# GSP.net
KiCad netlist of a schematic drawn in EAGLE
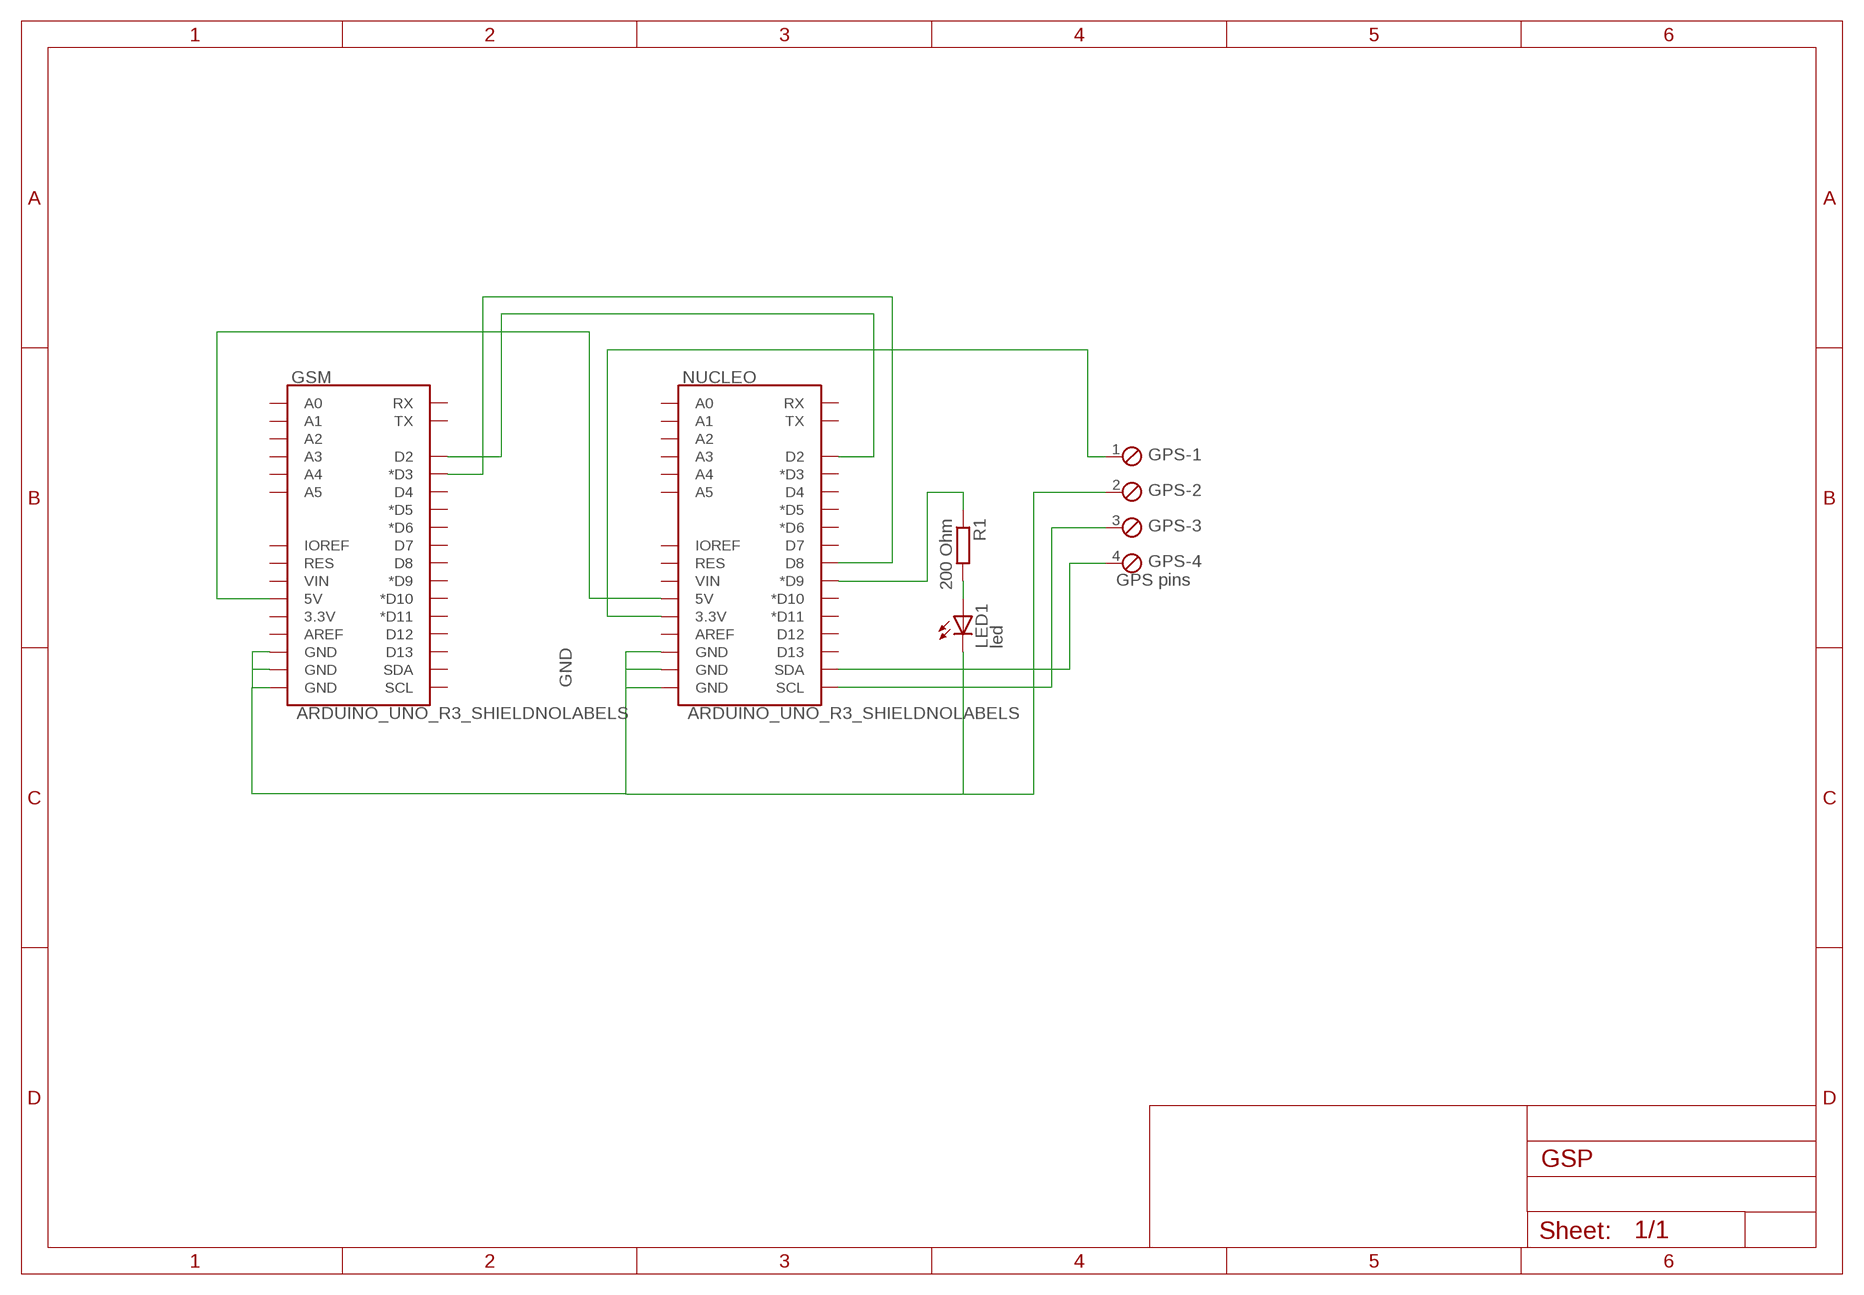
[diagram p0: schematic, sheet 1]

(export (version "E")
  (design (tool "Eeschema 10.0.6"))
  (components
    (comp (ref "GPS")
      (value "GPS pins")
      (footprint "eagle-import:4POL254")
      (libsource (lib "eagle-import") (part "MPT4"))
    )
    (comp (ref "GSM")
      (value "ARDUINO_UNO_R3_SHIELDNOLABELS")
      (footprint "eagle-import:UNO_R3_SHIELD_NOLABELS")
      (libsource (lib "eagle-import") (part "ARDUINO_UNO_R3_SHIELDNOLABELS"))
    )
    (comp (ref "LED1")
      (value "led")
      (footprint "eagle-import:LED3MM")
      (libsource (lib "eagle-import") (part "LED3MM"))
    )
    (comp (ref "NUCLEO")
      (value "ARDUINO_UNO_R3_SHIELDNOLABELS")
      (footprint "eagle-import:UNO_R3_SHIELD_NOLABELS")
      (libsource (lib "eagle-import") (part "ARDUINO_UNO_R3_SHIELDNOLABELS"))
    )
    (comp (ref "R1")
      (value "200 Ohm")
      (footprint "eagle-import:0204_5")
      (libsource (lib "eagle-import") (part "R-EU_0204/5"))
    )
  )
  (nets
    (net (code "1") (name "/GND") (class "Default")
      (node (ref "GPS") (pin "2") (pinfunction "1_2") (pintype "passive"))
      (node (ref "GSM") (pin "GND@0") (pinfunction "GND_GND@0") (pintype "bidirectional"))
      (node (ref "GSM") (pin "GND@1") (pinfunction "GND_GND@1") (pintype "bidirectional"))
      (node (ref "GSM") (pin "GND@2") (pinfunction "GND_GND@2") (pintype "bidirectional"))
      (node (ref "LED1") (pin "K") (pinfunction "C_K") (pintype "passive"))
      (node (ref "NUCLEO") (pin "GND@0") (pinfunction "GND_GND@0") (pintype "bidirectional"))
      (node (ref "NUCLEO") (pin "GND@1") (pinfunction "GND_GND@1") (pintype "bidirectional"))
      (node (ref "NUCLEO") (pin "GND@2") (pinfunction "GND_GND@2") (pintype "bidirectional"))
    )
    (net (code "2") (name "Net-(GPS-Pad1)") (class "Default")
      (node (ref "GPS") (pin "1") (pinfunction "1_1") (pintype "passive"))
      (node (ref "NUCLEO") (pin "3.3V") (pinfunction "3.3V_3.3V") (pintype "bidirectional"))
    )
    (net (code "3") (name "Net-(GPSC-1)") (class "Default")
      (node (ref "GPS") (pin "3") (pinfunction "1_3") (pintype "passive"))
      (node (ref "NUCLEO") (pin "SCL") (pinfunction "SCL_SCL") (pintype "bidirectional"))
    )
    (net (code "4") (name "Net-(GPSD-1)") (class "Default")
      (node (ref "GPS") (pin "4") (pinfunction "1_4") (pintype "passive"))
      (node (ref "NUCLEO") (pin "SDA") (pinfunction "SDA_SDA") (pintype "bidirectional"))
    )
    (net (code "5") (name "Net-(GSM-*D3)") (class "Default")
      (node (ref "GSM") (pin "D3") (pinfunction "*D3_D3") (pintype "bidirectional"))
      (node (ref "NUCLEO") (pin "D8") (pinfunction "D8_D8") (pintype "bidirectional"))
    )
    (net (code "6") (name "Net-(GSM-Pad5V)") (class "Default")
      (node (ref "GSM") (pin "5V") (pinfunction "5V_5V") (pintype "bidirectional"))
      (node (ref "NUCLEO") (pin "5V") (pinfunction "5V_5V") (pintype "bidirectional"))
    )
    (net (code "7") (name "Net-(GSM-PadD2)") (class "Default")
      (node (ref "GSM") (pin "D2") (pinfunction "D2_D2") (pintype "bidirectional"))
      (node (ref "NUCLEO") (pin "D2") (pinfunction "D2_D2") (pintype "bidirectional"))
    )
    (net (code "8") (name "Net-(LED1-PadA)") (class "Default")
      (node (ref "LED1") (pin "A") (pinfunction "A_A") (pintype "passive"))
      (node (ref "R1") (pin "2") (pinfunction "2_2") (pintype "passive"))
    )
    (net (code "9") (name "Net-(NUCLEO-*D9)") (class "Default")
      (node (ref "NUCLEO") (pin "D9") (pinfunction "*D9_D9") (pintype "bidirectional"))
      (node (ref "R1") (pin "1") (pinfunction "1_1") (pintype "passive"))
    )
    (net (code "10") (name "unconnected-(GSM-*D5-PadD5)") (class "Default")
      (node (ref "GSM") (pin "D5") (pinfunction "*D5_D5") (pintype "bidirectional"))
    )
    (net (code "11") (name "unconnected-(GSM-*D6-PadD6)") (class "Default")
      (node (ref "GSM") (pin "D6") (pinfunction "*D6_D6") (pintype "bidirectional"))
    )
    (net (code "12") (name "unconnected-(GSM-*D9-PadD9)") (class "Default")
      (node (ref "GSM") (pin "D9") (pinfunction "*D9_D9") (pintype "bidirectional"))
    )
    (net (code "13") (name "unconnected-(GSM-*D10-PadD10)") (class "Default")
      (node (ref "GSM") (pin "D10") (pinfunction "*D10_D10") (pintype "bidirectional"))
    )
    (net (code "14") (name "unconnected-(GSM-*D11-PadD11)") (class "Default")
      (node (ref "GSM") (pin "D11") (pinfunction "*D11_D11") (pintype "bidirectional"))
    )
    (net (code "15") (name "unconnected-(GSM-Pad3.3V)") (class "Default")
      (node (ref "GSM") (pin "3.3V") (pinfunction "3.3V_3.3V") (pintype "bidirectional"))
    )
    (net (code "16") (name "unconnected-(GSM-PadA0)") (class "Default")
      (node (ref "GSM") (pin "A0") (pinfunction "A0_A0") (pintype "bidirectional"))
    )
    (net (code "17") (name "unconnected-(GSM-PadA1)") (class "Default")
      (node (ref "GSM") (pin "A1") (pinfunction "A1_A1") (pintype "bidirectional"))
    )
    (net (code "18") (name "unconnected-(GSM-PadA2)") (class "Default")
      (node (ref "GSM") (pin "A2") (pinfunction "A2_A2") (pintype "bidirectional"))
    )
    (net (code "19") (name "unconnected-(GSM-PadA3)") (class "Default")
      (node (ref "GSM") (pin "A3") (pinfunction "A3_A3") (pintype "bidirectional"))
    )
    (net (code "20") (name "unconnected-(GSM-PadA4)") (class "Default")
      (node (ref "GSM") (pin "A4") (pinfunction "A4_A4") (pintype "bidirectional"))
    )
    (net (code "21") (name "unconnected-(GSM-PadA5)") (class "Default")
      (node (ref "GSM") (pin "A5") (pinfunction "A5_A5") (pintype "bidirectional"))
    )
    (net (code "22") (name "unconnected-(GSM-PadAREF)") (class "Default")
      (node (ref "GSM") (pin "AREF") (pinfunction "AREF_AREF") (pintype "bidirectional"))
    )
    (net (code "23") (name "unconnected-(GSM-PadD4)") (class "Default")
      (node (ref "GSM") (pin "D4") (pinfunction "D4_D4") (pintype "bidirectional"))
    )
    (net (code "24") (name "unconnected-(GSM-PadD7)") (class "Default")
      (node (ref "GSM") (pin "D7") (pinfunction "D7_D7") (pintype "bidirectional"))
    )
    (net (code "25") (name "unconnected-(GSM-PadD8)") (class "Default")
      (node (ref "GSM") (pin "D8") (pinfunction "D8_D8") (pintype "bidirectional"))
    )
    (net (code "26") (name "unconnected-(GSM-PadD12)") (class "Default")
      (node (ref "GSM") (pin "D12") (pinfunction "D12_D12") (pintype "bidirectional"))
    )
    (net (code "27") (name "unconnected-(GSM-PadD13)") (class "Default")
      (node (ref "GSM") (pin "D13") (pinfunction "D13_D13") (pintype "bidirectional"))
    )
    (net (code "28") (name "unconnected-(GSM-PadIOREF)") (class "Default")
      (node (ref "GSM") (pin "IOREF") (pinfunction "IOREF_IOREF") (pintype "bidirectional"))
    )
    (net (code "29") (name "unconnected-(GSM-PadRES)") (class "Default")
      (node (ref "GSM") (pin "RES") (pinfunction "RES_RES") (pintype "bidirectional"))
    )
    (net (code "30") (name "unconnected-(GSM-PadRX)") (class "Default")
      (node (ref "GSM") (pin "RX") (pinfunction "RX_RX") (pintype "bidirectional"))
    )
    (net (code "31") (name "unconnected-(GSM-PadSCL)") (class "Default")
      (node (ref "GSM") (pin "SCL") (pinfunction "SCL_SCL") (pintype "bidirectional"))
    )
    (net (code "32") (name "unconnected-(GSM-PadSDA)") (class "Default")
      (node (ref "GSM") (pin "SDA") (pinfunction "SDA_SDA") (pintype "bidirectional"))
    )
    (net (code "33") (name "unconnected-(GSM-PadTX)") (class "Default")
      (node (ref "GSM") (pin "TX") (pinfunction "TX_TX") (pintype "bidirectional"))
    )
    (net (code "34") (name "unconnected-(GSM-PadVIN)") (class "Default")
      (node (ref "GSM") (pin "VIN") (pinfunction "VIN_VIN") (pintype "bidirectional"))
    )
    (net (code "35") (name "unconnected-(NUCLEO-*D3-PadD3)") (class "Default")
      (node (ref "NUCLEO") (pin "D3") (pinfunction "*D3_D3") (pintype "bidirectional"))
    )
    (net (code "36") (name "unconnected-(NUCLEO-*D5-PadD5)") (class "Default")
      (node (ref "NUCLEO") (pin "D5") (pinfunction "*D5_D5") (pintype "bidirectional"))
    )
    (net (code "37") (name "unconnected-(NUCLEO-*D6-PadD6)") (class "Default")
      (node (ref "NUCLEO") (pin "D6") (pinfunction "*D6_D6") (pintype "bidirectional"))
    )
    (net (code "38") (name "unconnected-(NUCLEO-*D10-PadD10)") (class "Default")
      (node (ref "NUCLEO") (pin "D10") (pinfunction "*D10_D10") (pintype "bidirectional"))
    )
    (net (code "39") (name "unconnected-(NUCLEO-*D11-PadD11)") (class "Default")
      (node (ref "NUCLEO") (pin "D11") (pinfunction "*D11_D11") (pintype "bidirectional"))
    )
    (net (code "40") (name "unconnected-(NUCLEO-PadA0)") (class "Default")
      (node (ref "NUCLEO") (pin "A0") (pinfunction "A0_A0") (pintype "bidirectional"))
    )
    (net (code "41") (name "unconnected-(NUCLEO-PadA1)") (class "Default")
      (node (ref "NUCLEO") (pin "A1") (pinfunction "A1_A1") (pintype "bidirectional"))
    )
    (net (code "42") (name "unconnected-(NUCLEO-PadA2)") (class "Default")
      (node (ref "NUCLEO") (pin "A2") (pinfunction "A2_A2") (pintype "bidirectional"))
    )
    (net (code "43") (name "unconnected-(NUCLEO-PadA3)") (class "Default")
      (node (ref "NUCLEO") (pin "A3") (pinfunction "A3_A3") (pintype "bidirectional"))
    )
    (net (code "44") (name "unconnected-(NUCLEO-PadA4)") (class "Default")
      (node (ref "NUCLEO") (pin "A4") (pinfunction "A4_A4") (pintype "bidirectional"))
    )
    (net (code "45") (name "unconnected-(NUCLEO-PadA5)") (class "Default")
      (node (ref "NUCLEO") (pin "A5") (pinfunction "A5_A5") (pintype "bidirectional"))
    )
    (net (code "46") (name "unconnected-(NUCLEO-PadAREF)") (class "Default")
      (node (ref "NUCLEO") (pin "AREF") (pinfunction "AREF_AREF") (pintype "bidirectional"))
    )
    (net (code "47") (name "unconnected-(NUCLEO-PadD4)") (class "Default")
      (node (ref "NUCLEO") (pin "D4") (pinfunction "D4_D4") (pintype "bidirectional"))
    )
    (net (code "48") (name "unconnected-(NUCLEO-PadD7)") (class "Default")
      (node (ref "NUCLEO") (pin "D7") (pinfunction "D7_D7") (pintype "bidirectional"))
    )
    (net (code "49") (name "unconnected-(NUCLEO-PadD12)") (class "Default")
      (node (ref "NUCLEO") (pin "D12") (pinfunction "D12_D12") (pintype "bidirectional"))
    )
    (net (code "50") (name "unconnected-(NUCLEO-PadD13)") (class "Default")
      (node (ref "NUCLEO") (pin "D13") (pinfunction "D13_D13") (pintype "bidirectional"))
    )
    (net (code "51") (name "unconnected-(NUCLEO-PadIOREF)") (class "Default")
      (node (ref "NUCLEO") (pin "IOREF") (pinfunction "IOREF_IOREF") (pintype "bidirectional"))
    )
    (net (code "52") (name "unconnected-(NUCLEO-PadRES)") (class "Default")
      (node (ref "NUCLEO") (pin "RES") (pinfunction "RES_RES") (pintype "bidirectional"))
    )
    (net (code "53") (name "unconnected-(NUCLEO-PadRX)") (class "Default")
      (node (ref "NUCLEO") (pin "RX") (pinfunction "RX_RX") (pintype "bidirectional"))
    )
    (net (code "54") (name "unconnected-(NUCLEO-PadTX)") (class "Default")
      (node (ref "NUCLEO") (pin "TX") (pinfunction "TX_TX") (pintype "bidirectional"))
    )
    (net (code "55") (name "unconnected-(NUCLEO-PadVIN)") (class "Default")
      (node (ref "NUCLEO") (pin "VIN") (pinfunction "VIN_VIN") (pintype "bidirectional"))
    )
  )
)
